# connector.net
KiCad netlist of a schematic drawn in Altium Designer
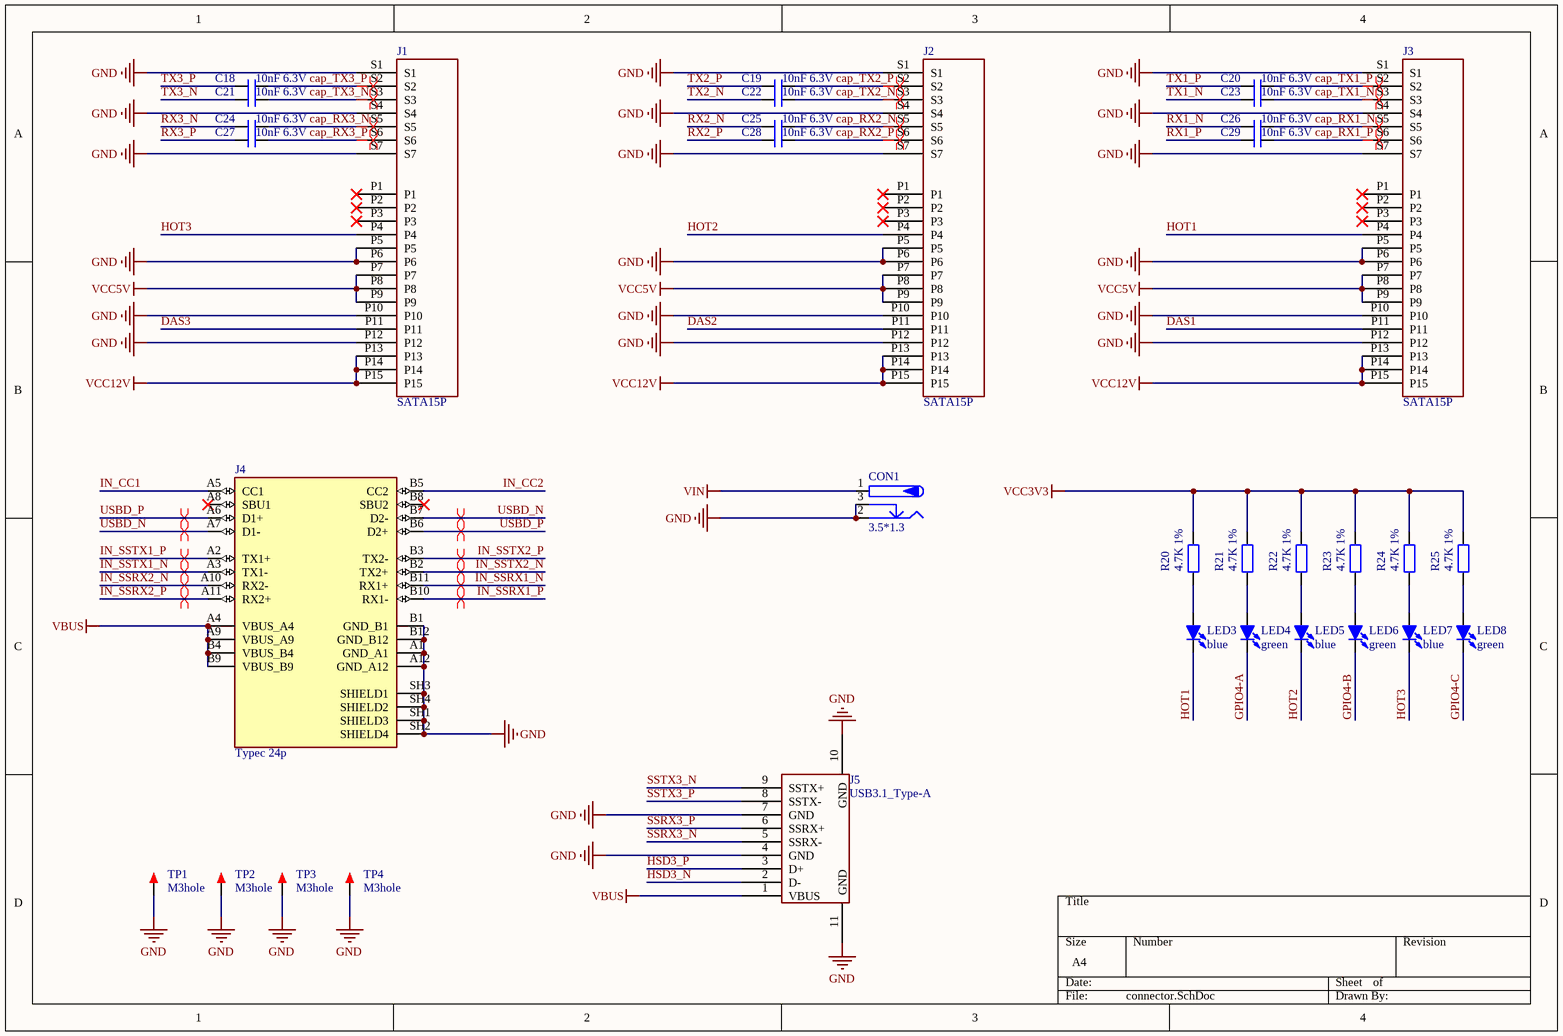
[diagram p0: connector.SchDoc]

(export (version "E")
  (design (tool "Eeschema 10.0.6"))
  (components
    (comp (ref "C18")
      (value "10nF 6.3V")
      (footprint "C0402_L")
      (description "无极性贴片电容")
      (fields (field (name "版权归属") "源创客"))
      (libsource (lib "Capacitor") (part "C"))
    )
    (comp (ref "C19")
      (value "10nF 6.3V")
      (footprint "C0402_L")
      (description "无极性贴片电容")
      (fields (field (name "版权归属") "源创客"))
      (libsource (lib "Capacitor") (part "C"))
    )
    (comp (ref "C20")
      (value "10nF 6.3V")
      (footprint "C0402_L")
      (description "无极性贴片电容")
      (fields (field (name "版权归属") "源创客"))
      (libsource (lib "Capacitor") (part "C"))
    )
    (comp (ref "C21")
      (value "10nF 6.3V")
      (footprint "C0402_L")
      (description "无极性贴片电容")
      (fields (field (name "版权归属") "源创客"))
      (libsource (lib "Capacitor") (part "C"))
    )
    (comp (ref "C22")
      (value "10nF 6.3V")
      (footprint "C0402_L")
      (description "无极性贴片电容")
      (fields (field (name "版权归属") "源创客"))
      (libsource (lib "Capacitor") (part "C"))
    )
    (comp (ref "C23")
      (value "10nF 6.3V")
      (footprint "C0402_L")
      (description "无极性贴片电容")
      (fields (field (name "版权归属") "源创客"))
      (libsource (lib "Capacitor") (part "C"))
    )
    (comp (ref "C24")
      (value "10nF 6.3V")
      (footprint "C0402_L")
      (description "无极性贴片电容")
      (fields (field (name "版权归属") "源创客"))
      (libsource (lib "Capacitor") (part "C"))
    )
    (comp (ref "C25")
      (value "10nF 6.3V")
      (footprint "C0402_L")
      (description "无极性贴片电容")
      (fields (field (name "版权归属") "源创客"))
      (libsource (lib "Capacitor") (part "C"))
    )
    (comp (ref "C26")
      (value "10nF 6.3V")
      (footprint "C0402_L")
      (description "无极性贴片电容")
      (fields (field (name "版权归属") "源创客"))
      (libsource (lib "Capacitor") (part "C"))
    )
    (comp (ref "C27")
      (value "10nF 6.3V")
      (footprint "C0402_L")
      (description "无极性贴片电容")
      (fields (field (name "版权归属") "源创客"))
      (libsource (lib "Capacitor") (part "C"))
    )
    (comp (ref "C28")
      (value "10nF 6.3V")
      (footprint "C0402_L")
      (description "无极性贴片电容")
      (fields (field (name "版权归属") "源创客"))
      (libsource (lib "Capacitor") (part "C"))
    )
    (comp (ref "C29")
      (value "10nF 6.3V")
      (footprint "C0402_L")
      (description "无极性贴片电容")
      (fields (field (name "版权归属") "源创客"))
      (libsource (lib "Capacitor") (part "C"))
    )
    (comp (ref "CON1")
      (value "3.5*1.3")
      (footprint "DC-012")
      (description "低压电源接口")
      (fields (field (name "版权归属") "源创客"))
      (libsource (lib "Connector-PWR") (part "P-DC"))
    )
    (comp (ref "J1")
      (value "SATA15P")
      (footprint "SATA 15P 贴片")
      (libsource (lib "Connector-SATA&SAS") (part "SATA15P"))
    )
    (comp (ref "J2")
      (value "SATA15P")
      (footprint "SATA 15P 贴片")
      (libsource (lib "Connector-SATA&SAS") (part "SATA15P"))
    )
    (comp (ref "J3")
      (value "SATA15P")
      (footprint "SATA 15P 贴片")
      (libsource (lib "Connector-SATA&SAS") (part "SATA15P"))
    )
    (comp (ref "J4")
      (value "Typec 24p")
      (footprint "TypeC 24p 直立")
      (fields (field (name "MF") "Molex") (field (name "MP") "1054500101"))
      (libsource (lib "Connector-USB") (part "Typec 24p"))
    )
    (comp (ref "J5")
      (value "USB3.1_Type-A")
      (footprint "USB3.1_Type-A 立式直插")
      (description "USB接口")
      (libsource (lib "Connector-USB") (part "USB3.1_Type-A"))
    )
    (comp (ref "LED3")
      (value "blue")
      (footprint "LED 0805B")
      (description "插件LED")
      (fields (field (name "版权归属") "源创客"))
      (libsource (lib "LED") (part "LED-3MM"))
    )
    (comp (ref "LED4")
      (value "green")
      (footprint "LED 0805G")
      (description "插件LED")
      (fields (field (name "版权归属") "源创客"))
      (libsource (lib "LED") (part "LED-3MM"))
    )
    (comp (ref "LED5")
      (value "blue")
      (footprint "LED 0805B")
      (description "插件LED")
      (fields (field (name "版权归属") "源创客"))
      (libsource (lib "LED") (part "LED-3MM"))
    )
    (comp (ref "LED6")
      (value "green")
      (footprint "LED 0805G")
      (description "插件LED")
      (fields (field (name "版权归属") "源创客"))
      (libsource (lib "LED") (part "LED-3MM"))
    )
    (comp (ref "LED7")
      (value "blue")
      (footprint "LED 0805B")
      (description "插件LED")
      (fields (field (name "版权归属") "源创客"))
      (libsource (lib "LED") (part "LED-3MM"))
    )
    (comp (ref "LED8")
      (value "green")
      (footprint "LED 0805G")
      (description "插件LED")
      (fields (field (name "版权归属") "源创客"))
      (libsource (lib "LED") (part "LED-3MM"))
    )
    (comp (ref "R20")
      (value "4.7K 1%")
      (footprint "R0402_L")
      (description "贴片电阻")
      (fields (field (name "版权归属") "源创客"))
      (libsource (lib "Resistor") (part "R"))
    )
    (comp (ref "R21")
      (value "4.7K 1%")
      (footprint "R0402_L")
      (description "贴片电阻")
      (fields (field (name "版权归属") "源创客"))
      (libsource (lib "Resistor") (part "R"))
    )
    (comp (ref "R22")
      (value "4.7K 1%")
      (footprint "R0402_L")
      (description "贴片电阻")
      (fields (field (name "版权归属") "源创客"))
      (libsource (lib "Resistor") (part "R"))
    )
    (comp (ref "R23")
      (value "4.7K 1%")
      (footprint "R0402_L")
      (description "贴片电阻")
      (fields (field (name "版权归属") "源创客"))
      (libsource (lib "Resistor") (part "R"))
    )
    (comp (ref "R24")
      (value "4.7K 1%")
      (footprint "R0402_L")
      (description "贴片电阻")
      (fields (field (name "版权归属") "源创客"))
      (libsource (lib "Resistor") (part "R"))
    )
    (comp (ref "R25")
      (value "4.7K 1%")
      (footprint "R0402_L")
      (description "贴片电阻")
      (fields (field (name "版权归属") "源创客"))
      (libsource (lib "Resistor") (part "R"))
    )
    (comp (ref "TP1")
      (value "M3hole")
      (footprint "m3内嵌螺母贴片")
      (description "测试点")
      (fields (field (name "版权归属") "源创客"))
      (libsource (lib "Hole") (part "TEST"))
    )
    (comp (ref "TP2")
      (value "M3hole")
      (footprint "m3内嵌螺母贴片")
      (description "测试点")
      (fields (field (name "版权归属") "源创客"))
      (libsource (lib "Hole") (part "TEST"))
    )
    (comp (ref "TP3")
      (value "M3hole")
      (footprint "m3内嵌螺母贴片")
      (description "测试点")
      (fields (field (name "版权归属") "源创客"))
      (libsource (lib "Hole") (part "TEST"))
    )
    (comp (ref "TP4")
      (value "M3hole")
      (footprint "m3内嵌螺母贴片")
      (description "测试点")
      (fields (field (name "版权归属") "源创客"))
      (libsource (lib "Hole") (part "TEST"))
    )
  )
  (nets
    (net (code "1") (name "/DAS1") (class "Default")
      (node (ref "J3") (pin "P11") (pinfunction "P11_P11") (pintype "passive"))
    )
    (net (code "2") (name "/DAS2") (class "Default")
      (node (ref "J2") (pin "P11") (pinfunction "P11_P11") (pintype "passive"))
    )
    (net (code "3") (name "/DAS3") (class "Default")
      (node (ref "J1") (pin "P11") (pinfunction "P11_P11") (pintype "passive"))
    )
    (net (code "4") (name "/GPIO4-A") (class "Default")
      (node (ref "LED4") (pin "2") (pinfunction "K_2") (pintype "passive"))
    )
    (net (code "5") (name "/GPIO4-B") (class "Default")
      (node (ref "LED6") (pin "2") (pinfunction "K_2") (pintype "passive"))
    )
    (net (code "6") (name "/GPIO4-C") (class "Default")
      (node (ref "LED8") (pin "2") (pinfunction "K_2") (pintype "passive"))
    )
    (net (code "7") (name "/HOT1") (class "Default")
      (node (ref "J3") (pin "P4") (pinfunction "P4_P4") (pintype "passive"))
      (node (ref "LED3") (pin "2") (pinfunction "K_2") (pintype "passive"))
    )
    (net (code "8") (name "/HOT2") (class "Default")
      (node (ref "J2") (pin "P4") (pinfunction "P4_P4") (pintype "passive"))
      (node (ref "LED5") (pin "2") (pinfunction "K_2") (pintype "passive"))
    )
    (net (code "9") (name "/HOT3") (class "Default")
      (node (ref "J1") (pin "P4") (pinfunction "P4_P4") (pintype "passive"))
      (node (ref "LED7") (pin "2") (pinfunction "K_2") (pintype "passive"))
    )
    (net (code "10") (name "/HSD3_N") (class "Default")
      (node (ref "J5") (pin "2") (pinfunction "D-_2") (pintype "passive"))
    )
    (net (code "11") (name "/HSD3_P") (class "Default")
      (node (ref "J5") (pin "3") (pinfunction "D+_3") (pintype "passive"))
    )
    (net (code "12") (name "/IN_CC1") (class "Default")
      (node (ref "J4") (pin "A5") (pinfunction "CC1_A5") (pintype "bidirectional"))
    )
    (net (code "13") (name "/IN_CC2") (class "Default")
      (node (ref "J4") (pin "B5") (pinfunction "CC2_B5") (pintype "bidirectional"))
    )
    (net (code "14") (name "/IN_SSRX1_N") (class "Default")
      (node (ref "J4") (pin "B11") (pinfunction "RX1+_B11") (pintype "bidirectional"))
    )
    (net (code "15") (name "/IN_SSRX1_P") (class "Default")
      (node (ref "J4") (pin "B10") (pinfunction "RX1-_B10") (pintype "bidirectional"))
    )
    (net (code "16") (name "/IN_SSRX2_N") (class "Default")
      (node (ref "J4") (pin "A10") (pinfunction "RX2-_A10") (pintype "bidirectional"))
    )
    (net (code "17") (name "/IN_SSRX2_P") (class "Default")
      (node (ref "J4") (pin "A11") (pinfunction "RX2+_A11") (pintype "bidirectional"))
    )
    (net (code "18") (name "/IN_SSTX1_N") (class "Default")
      (node (ref "J4") (pin "A3") (pinfunction "TX1-_A3") (pintype "bidirectional"))
    )
    (net (code "19") (name "/IN_SSTX1_P") (class "Default")
      (node (ref "J4") (pin "A2") (pinfunction "TX1+_A2") (pintype "bidirectional"))
    )
    (net (code "20") (name "/IN_SSTX2_N") (class "Default")
      (node (ref "J4") (pin "B2") (pinfunction "TX2+_B2") (pintype "bidirectional"))
    )
    (net (code "21") (name "/IN_SSTX2_P") (class "Default")
      (node (ref "J4") (pin "B3") (pinfunction "TX2-_B3") (pintype "bidirectional"))
    )
    (net (code "22") (name "/RX1_N") (class "Default")
      (node (ref "C26") (pin "2") (pinfunction "2_2") (pintype "passive"))
    )
    (net (code "23") (name "/RX1_P") (class "Default")
      (node (ref "C29") (pin "2") (pinfunction "2_2") (pintype "passive"))
    )
    (net (code "24") (name "/RX2_N") (class "Default")
      (node (ref "C25") (pin "2") (pinfunction "2_2") (pintype "passive"))
    )
    (net (code "25") (name "/RX2_P") (class "Default")
      (node (ref "C28") (pin "2") (pinfunction "2_2") (pintype "passive"))
    )
    (net (code "26") (name "/RX3_N") (class "Default")
      (node (ref "C24") (pin "2") (pinfunction "2_2") (pintype "passive"))
    )
    (net (code "27") (name "/RX3_P") (class "Default")
      (node (ref "C27") (pin "2") (pinfunction "2_2") (pintype "passive"))
    )
    (net (code "28") (name "/SSRX3_N") (class "Default")
      (node (ref "J5") (pin "5") (pinfunction "SSRX-_5") (pintype "passive"))
    )
    (net (code "29") (name "/SSRX3_P") (class "Default")
      (node (ref "J5") (pin "6") (pinfunction "SSRX+_6") (pintype "passive"))
    )
    (net (code "30") (name "/SSTX3_N") (class "Default")
      (node (ref "J5") (pin "9") (pinfunction "SSTX+_9") (pintype "passive"))
    )
    (net (code "31") (name "/SSTX3_P") (class "Default")
      (node (ref "J5") (pin "8") (pinfunction "SSTX-_8") (pintype "passive"))
    )
    (net (code "32") (name "/TX1_N") (class "Default")
      (node (ref "C23") (pin "2") (pinfunction "2_2") (pintype "passive"))
    )
    (net (code "33") (name "/TX1_P") (class "Default")
      (node (ref "C20") (pin "2") (pinfunction "2_2") (pintype "passive"))
    )
    (net (code "34") (name "/TX2_N") (class "Default")
      (node (ref "C22") (pin "2") (pinfunction "2_2") (pintype "passive"))
    )
    (net (code "35") (name "/TX2_P") (class "Default")
      (node (ref "C19") (pin "2") (pinfunction "2_2") (pintype "passive"))
    )
    (net (code "36") (name "/TX3_N") (class "Default")
      (node (ref "C21") (pin "2") (pinfunction "2_2") (pintype "passive"))
    )
    (net (code "37") (name "/TX3_P") (class "Default")
      (node (ref "C18") (pin "2") (pinfunction "2_2") (pintype "passive"))
    )
    (net (code "38") (name "/USBD_N") (class "Default")
      (node (ref "J4") (pin "A7") (pinfunction "D1-_A7") (pintype "bidirectional"))
      (node (ref "J4") (pin "B7") (pinfunction "D2-_B7") (pintype "bidirectional"))
    )
    (net (code "39") (name "/USBD_P") (class "Default")
      (node (ref "J4") (pin "A6") (pinfunction "D1+_A6") (pintype "bidirectional"))
      (node (ref "J4") (pin "B6") (pinfunction "D2+_B6") (pintype "bidirectional"))
    )
    (net (code "40") (name "/cap_RX1_N") (class "Default")
      (node (ref "C26") (pin "1") (pinfunction "1_1") (pintype "passive"))
      (node (ref "J3") (pin "S5") (pinfunction "S5_S5") (pintype "passive"))
    )
    (net (code "41") (name "/cap_RX1_P") (class "Default")
      (node (ref "C29") (pin "1") (pinfunction "1_1") (pintype "passive"))
      (node (ref "J3") (pin "S6") (pinfunction "S6_S6") (pintype "passive"))
    )
    (net (code "42") (name "/cap_RX2_N") (class "Default")
      (node (ref "C25") (pin "1") (pinfunction "1_1") (pintype "passive"))
      (node (ref "J2") (pin "S5") (pinfunction "S5_S5") (pintype "passive"))
    )
    (net (code "43") (name "/cap_RX2_P") (class "Default")
      (node (ref "C28") (pin "1") (pinfunction "1_1") (pintype "passive"))
      (node (ref "J2") (pin "S6") (pinfunction "S6_S6") (pintype "passive"))
    )
    (net (code "44") (name "/cap_RX3_N") (class "Default")
      (node (ref "C24") (pin "1") (pinfunction "1_1") (pintype "passive"))
      (node (ref "J1") (pin "S5") (pinfunction "S5_S5") (pintype "passive"))
    )
    (net (code "45") (name "/cap_RX3_P") (class "Default")
      (node (ref "C27") (pin "1") (pinfunction "1_1") (pintype "passive"))
      (node (ref "J1") (pin "S6") (pinfunction "S6_S6") (pintype "passive"))
    )
    (net (code "46") (name "/cap_TX1_N") (class "Default")
      (node (ref "C23") (pin "1") (pinfunction "1_1") (pintype "passive"))
      (node (ref "J3") (pin "S3") (pinfunction "S3_S3") (pintype "passive"))
    )
    (net (code "47") (name "/cap_TX1_P") (class "Default")
      (node (ref "C20") (pin "1") (pinfunction "1_1") (pintype "passive"))
      (node (ref "J3") (pin "S2") (pinfunction "S2_S2") (pintype "passive"))
    )
    (net (code "48") (name "/cap_TX2_N") (class "Default")
      (node (ref "C22") (pin "1") (pinfunction "1_1") (pintype "passive"))
      (node (ref "J2") (pin "S3") (pinfunction "S3_S3") (pintype "passive"))
    )
    (net (code "49") (name "/cap_TX2_P") (class "Default")
      (node (ref "C19") (pin "1") (pinfunction "1_1") (pintype "passive"))
      (node (ref "J2") (pin "S2") (pinfunction "S2_S2") (pintype "passive"))
    )
    (net (code "50") (name "/cap_TX3_N") (class "Default")
      (node (ref "C21") (pin "1") (pinfunction "1_1") (pintype "passive"))
      (node (ref "J1") (pin "S3") (pinfunction "S3_S3") (pintype "passive"))
    )
    (net (code "51") (name "/cap_TX3_P") (class "Default")
      (node (ref "C18") (pin "1") (pinfunction "1_1") (pintype "passive"))
      (node (ref "J1") (pin "S2") (pinfunction "S2_S2") (pintype "passive"))
    )
    (net (code "52") (name "GND") (class "Default")
      (node (ref "CON1") (pin "2") (pintype "power_in"))
      (node (ref "CON1") (pin "3") (pintype "power_in"))
      (node (ref "J1") (pin "P10") (pinfunction "P10_P10") (pintype "passive"))
      (node (ref "J1") (pin "P12") (pinfunction "P12_P12") (pintype "passive"))
      (node (ref "J1") (pin "P5") (pinfunction "P5_P5") (pintype "passive"))
      (node (ref "J1") (pin "P6") (pinfunction "P6_P6") (pintype "passive"))
      (node (ref "J1") (pin "S1") (pinfunction "S1_S1") (pintype "passive"))
      (node (ref "J1") (pin "S4") (pinfunction "S4_S4") (pintype "passive"))
      (node (ref "J1") (pin "S7") (pinfunction "S7_S7") (pintype "passive"))
      (node (ref "J2") (pin "P10") (pinfunction "P10_P10") (pintype "passive"))
      (node (ref "J2") (pin "P12") (pinfunction "P12_P12") (pintype "passive"))
      (node (ref "J2") (pin "P5") (pinfunction "P5_P5") (pintype "passive"))
      (node (ref "J2") (pin "P6") (pinfunction "P6_P6") (pintype "passive"))
      (node (ref "J2") (pin "S1") (pinfunction "S1_S1") (pintype "passive"))
      (node (ref "J2") (pin "S4") (pinfunction "S4_S4") (pintype "passive"))
      (node (ref "J2") (pin "S7") (pinfunction "S7_S7") (pintype "passive"))
      (node (ref "J3") (pin "P10") (pinfunction "P10_P10") (pintype "passive"))
      (node (ref "J3") (pin "P12") (pinfunction "P12_P12") (pintype "passive"))
      (node (ref "J3") (pin "P5") (pinfunction "P5_P5") (pintype "passive"))
      (node (ref "J3") (pin "P6") (pinfunction "P6_P6") (pintype "passive"))
      (node (ref "J3") (pin "S1") (pinfunction "S1_S1") (pintype "passive"))
      (node (ref "J3") (pin "S4") (pinfunction "S4_S4") (pintype "passive"))
      (node (ref "J3") (pin "S7") (pinfunction "S7_S7") (pintype "passive"))
      (node (ref "J4") (pin "A1") (pinfunction "GND_A1_A1") (pintype "power_in"))
      (node (ref "J4") (pin "A12") (pinfunction "GND_A12_A12") (pintype "power_in"))
      (node (ref "J4") (pin "B1") (pinfunction "GND_B1_B1") (pintype "power_in"))
      (node (ref "J4") (pin "B12") (pinfunction "GND_B12_B12") (pintype "power_in"))
      (node (ref "J4") (pin "SH1") (pinfunction "SHIELD3_SH1") (pintype "passive"))
      (node (ref "J4") (pin "SH2") (pinfunction "SHIELD4_SH2") (pintype "passive"))
      (node (ref "J4") (pin "SH3") (pinfunction "SHIELD1_SH3") (pintype "passive"))
      (node (ref "J4") (pin "SH4") (pinfunction "SHIELD2_SH4") (pintype "passive"))
      (node (ref "J5") (pin "10") (pinfunction "GND_10") (pintype "passive"))
      (node (ref "J5") (pin "11") (pinfunction "GND_11") (pintype "passive"))
      (node (ref "J5") (pin "4") (pinfunction "GND_4") (pintype "passive"))
      (node (ref "J5") (pin "7") (pinfunction "GND_7") (pintype "passive"))
      (node (ref "TP1") (pin "1") (pinfunction "1_1") (pintype "passive"))
      (node (ref "TP2") (pin "1") (pinfunction "1_1") (pintype "passive"))
      (node (ref "TP3") (pin "1") (pinfunction "1_1") (pintype "passive"))
      (node (ref "TP4") (pin "1") (pinfunction "1_1") (pintype "passive"))
    )
    (net (code "53") (name "Net-(LED3-A)") (class "Default")
      (node (ref "LED3") (pin "1") (pinfunction "A_1") (pintype "passive"))
      (node (ref "R20") (pin "2") (pinfunction "2_2") (pintype "passive"))
    )
    (net (code "54") (name "Net-(LED4-A)") (class "Default")
      (node (ref "LED4") (pin "1") (pinfunction "A_1") (pintype "passive"))
      (node (ref "R21") (pin "2") (pinfunction "2_2") (pintype "passive"))
    )
    (net (code "55") (name "Net-(LED5-A)") (class "Default")
      (node (ref "LED5") (pin "1") (pinfunction "A_1") (pintype "passive"))
      (node (ref "R22") (pin "2") (pinfunction "2_2") (pintype "passive"))
    )
    (net (code "56") (name "Net-(LED6-A)") (class "Default")
      (node (ref "LED6") (pin "1") (pinfunction "A_1") (pintype "passive"))
      (node (ref "R23") (pin "2") (pinfunction "2_2") (pintype "passive"))
    )
    (net (code "57") (name "Net-(LED7-A)") (class "Default")
      (node (ref "LED7") (pin "1") (pinfunction "A_1") (pintype "passive"))
      (node (ref "R24") (pin "2") (pinfunction "2_2") (pintype "passive"))
    )
    (net (code "58") (name "Net-(LED8-A)") (class "Default")
      (node (ref "LED8") (pin "1") (pinfunction "A_1") (pintype "passive"))
      (node (ref "R25") (pin "2") (pinfunction "2_2") (pintype "passive"))
    )
    (net (code "59") (name "VBUS") (class "Default")
      (node (ref "J4") (pin "A4") (pinfunction "VBUS_A4_A4") (pintype "power_in"))
      (node (ref "J4") (pin "A9") (pinfunction "VBUS_A9_A9") (pintype "power_in"))
      (node (ref "J4") (pin "B4") (pinfunction "VBUS_B4_B4") (pintype "power_in"))
      (node (ref "J4") (pin "B9") (pinfunction "VBUS_B9_B9") (pintype "power_in"))
      (node (ref "J5") (pin "1") (pinfunction "VBUS_1") (pintype "passive"))
    )
    (net (code "60") (name "VCC3V3") (class "Default")
      (node (ref "R20") (pin "1") (pinfunction "1_1") (pintype "passive"))
      (node (ref "R21") (pin "1") (pinfunction "1_1") (pintype "passive"))
      (node (ref "R22") (pin "1") (pinfunction "1_1") (pintype "passive"))
      (node (ref "R23") (pin "1") (pinfunction "1_1") (pintype "passive"))
      (node (ref "R24") (pin "1") (pinfunction "1_1") (pintype "passive"))
      (node (ref "R25") (pin "1") (pinfunction "1_1") (pintype "passive"))
    )
    (net (code "61") (name "VCC5V") (class "Default")
      (node (ref "J1") (pin "P7") (pinfunction "P7_P7") (pintype "passive"))
      (node (ref "J1") (pin "P8") (pinfunction "P8_P8") (pintype "passive"))
      (node (ref "J1") (pin "P9") (pinfunction "P9_P9") (pintype "passive"))
      (node (ref "J2") (pin "P7") (pinfunction "P7_P7") (pintype "passive"))
      (node (ref "J2") (pin "P8") (pinfunction "P8_P8") (pintype "passive"))
      (node (ref "J2") (pin "P9") (pinfunction "P9_P9") (pintype "passive"))
      (node (ref "J3") (pin "P7") (pinfunction "P7_P7") (pintype "passive"))
      (node (ref "J3") (pin "P8") (pinfunction "P8_P8") (pintype "passive"))
      (node (ref "J3") (pin "P9") (pinfunction "P9_P9") (pintype "passive"))
    )
    (net (code "62") (name "VCC12V") (class "Default")
      (node (ref "J1") (pin "P13") (pinfunction "P13_P13") (pintype "passive"))
      (node (ref "J1") (pin "P14") (pinfunction "P14_P14") (pintype "passive"))
      (node (ref "J1") (pin "P15") (pinfunction "P15_P15") (pintype "passive"))
      (node (ref "J2") (pin "P13") (pinfunction "P13_P13") (pintype "passive"))
      (node (ref "J2") (pin "P14") (pinfunction "P14_P14") (pintype "passive"))
      (node (ref "J2") (pin "P15") (pinfunction "P15_P15") (pintype "passive"))
      (node (ref "J3") (pin "P13") (pinfunction "P13_P13") (pintype "passive"))
      (node (ref "J3") (pin "P14") (pinfunction "P14_P14") (pintype "passive"))
      (node (ref "J3") (pin "P15") (pinfunction "P15_P15") (pintype "passive"))
    )
    (net (code "63") (name "VIN") (class "Default") (node (ref "CON1") (pin "1") (pintype "power_in")))
    (net (code "64") (name "unconnected-(J1-PadP1)") (class "Default")
      (node (ref "J1") (pin "P1") (pinfunction "P1_P1") (pintype "passive+no_connect"))
    )
    (net (code "65") (name "unconnected-(J1-PadP2)") (class "Default")
      (node (ref "J1") (pin "P2") (pinfunction "P2_P2") (pintype "passive+no_connect"))
    )
    (net (code "66") (name "unconnected-(J1-PadP3)") (class "Default")
      (node (ref "J1") (pin "P3") (pinfunction "P3_P3") (pintype "passive+no_connect"))
    )
    (net (code "67") (name "unconnected-(J2-PadP1)") (class "Default")
      (node (ref "J2") (pin "P1") (pinfunction "P1_P1") (pintype "passive+no_connect"))
    )
    (net (code "68") (name "unconnected-(J2-PadP2)") (class "Default")
      (node (ref "J2") (pin "P2") (pinfunction "P2_P2") (pintype "passive+no_connect"))
    )
    (net (code "69") (name "unconnected-(J2-PadP3)") (class "Default")
      (node (ref "J2") (pin "P3") (pinfunction "P3_P3") (pintype "passive+no_connect"))
    )
    (net (code "70") (name "unconnected-(J3-PadP1)") (class "Default")
      (node (ref "J3") (pin "P1") (pinfunction "P1_P1") (pintype "passive+no_connect"))
    )
    (net (code "71") (name "unconnected-(J3-PadP2)") (class "Default")
      (node (ref "J3") (pin "P2") (pinfunction "P2_P2") (pintype "passive+no_connect"))
    )
    (net (code "72") (name "unconnected-(J3-PadP3)") (class "Default")
      (node (ref "J3") (pin "P3") (pinfunction "P3_P3") (pintype "passive+no_connect"))
    )
    (net (code "73") (name "unconnected-(J4-SBU1-PadA8)") (class "Default")
      (node (ref "J4") (pin "A8") (pinfunction "SBU1_A8") (pintype "bidirectional+no_connect"))
    )
    (net (code "74") (name "unconnected-(J4-SBU2-PadB8)") (class "Default")
      (node (ref "J4") (pin "B8") (pinfunction "SBU2_B8") (pintype "bidirectional+no_connect"))
    )
  )
)
